# SH02_-_OMAP-L137_MCASP.net
KiCad netlist of a schematic drawn in Altium Designer
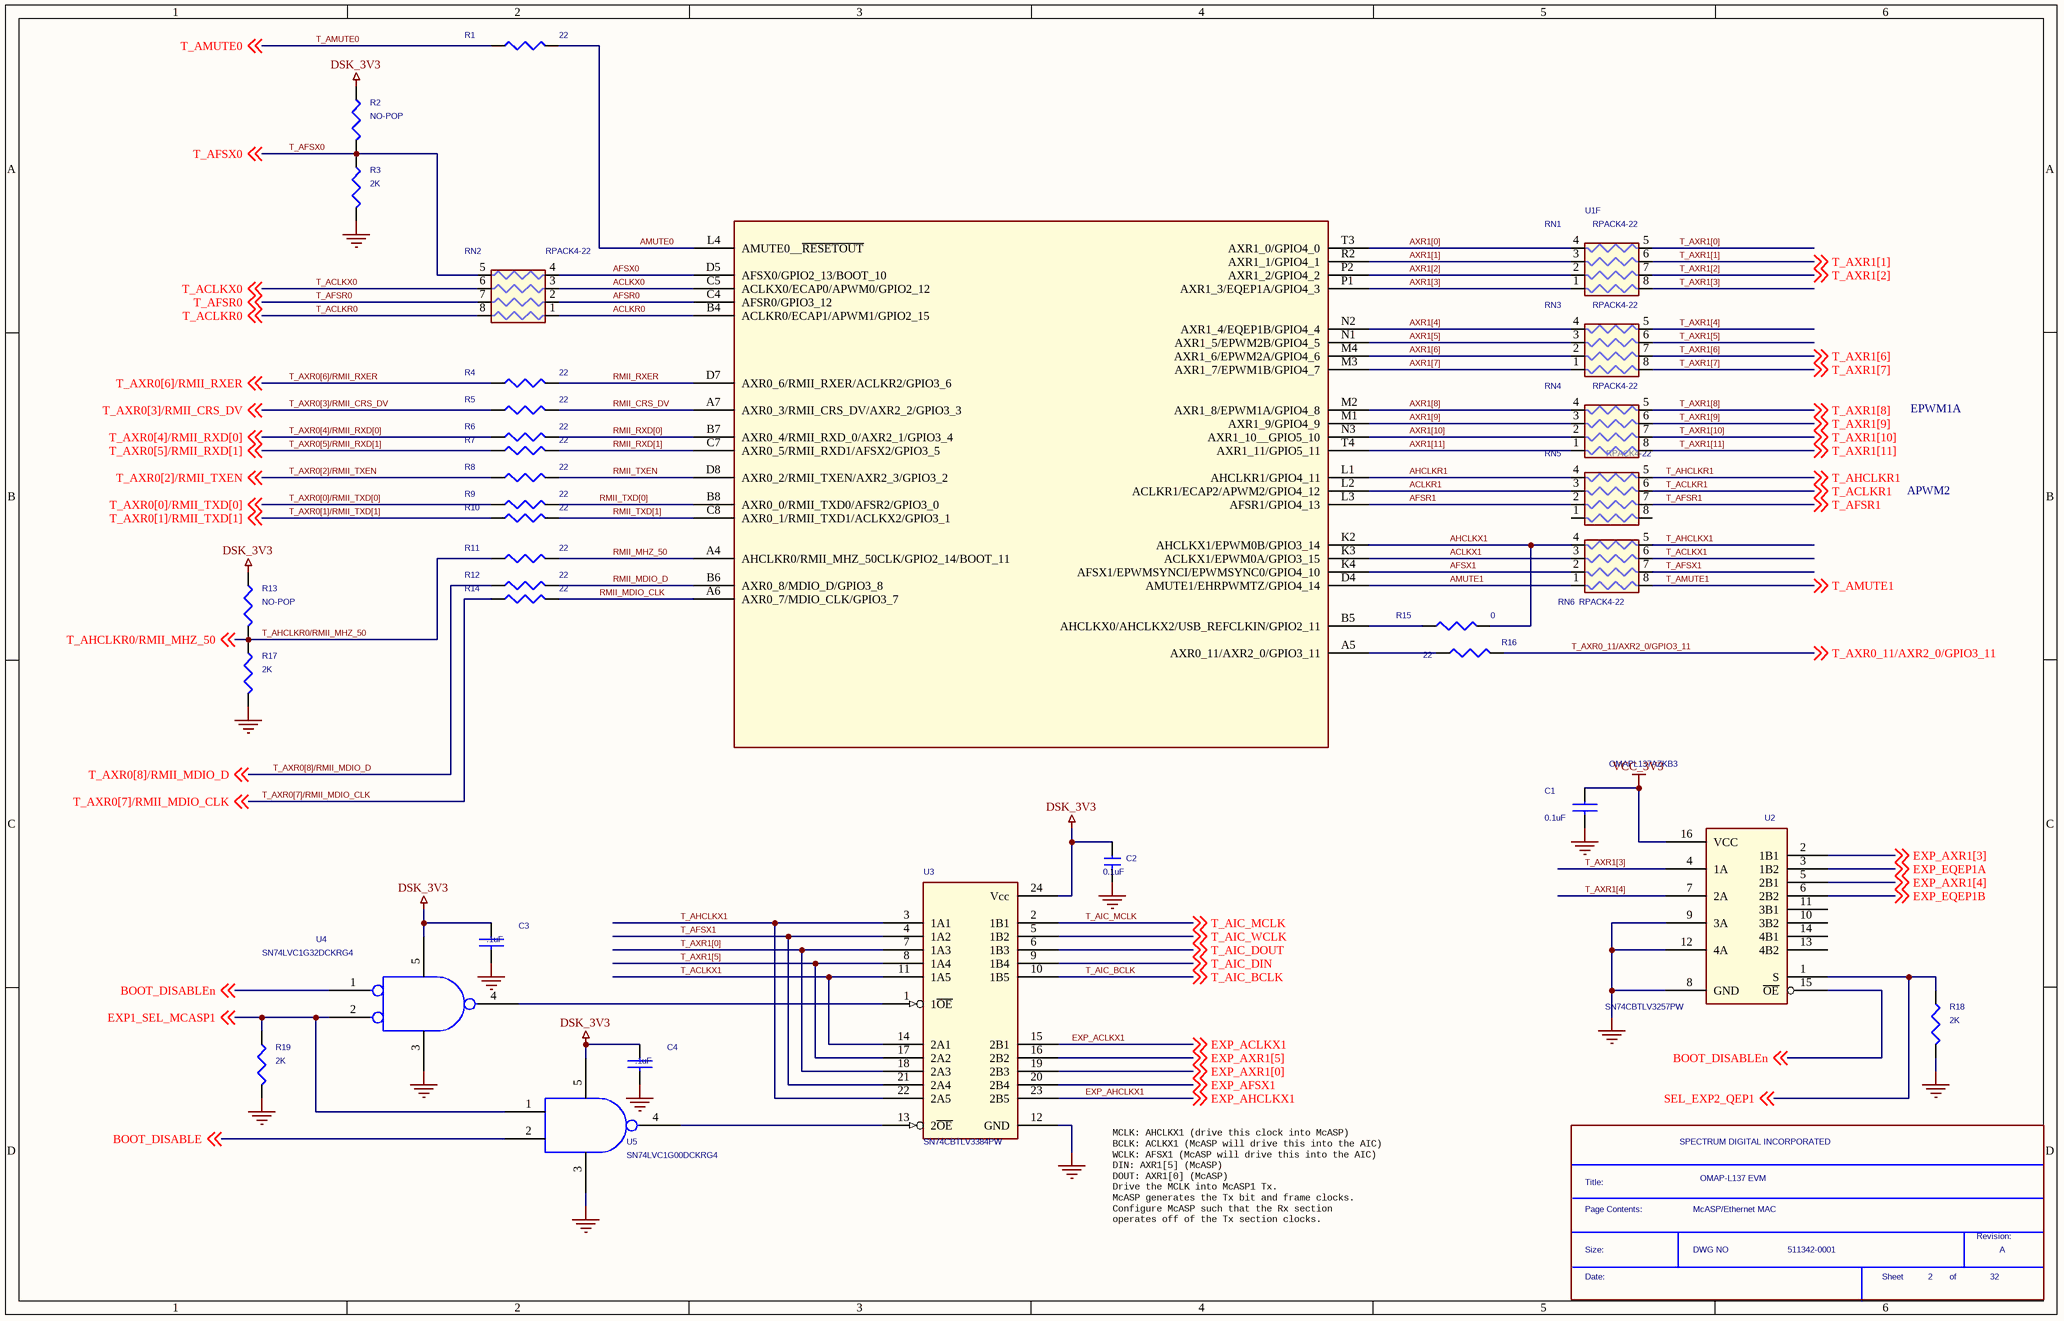
[diagram p0: SH02 - OMAP-L137 MCASP.SchDoc]

(export (version "E")
  (design (tool "Eeschema 10.0.6"))
  (components
    (comp (ref "C1")
      (value "0.1uF")
      (footprint "c402-25")
      (fields (field (name "PART #") "101587-1100R"))
      (libsource (lib "*") (part "CAP NP"))
    )
    (comp (ref "C2")
      (value "0.1uF")
      (footprint "c402-25")
      (fields (field (name "PART #") "101587-1100R"))
      (libsource (lib "*") (part "CAP NP_1"))
    )
    (comp (ref "C3")
      (value ".1uF")
      (footprint "c402-25")
      (fields (field (name "PART #") "101587-1100R"))
      (libsource (lib "*") (part "CAP NP_2"))
    )
    (comp (ref "C4")
      (value ".1uF")
      (footprint "c402-25")
      (fields (field (name "PART #") "101587-1100R"))
      (libsource (lib "*") (part "CAP NP_2"))
    )
    (comp (ref "R1")
      (value "22")
      (footprint "r402-25")
      (fields (field (name "PART #") "101370-2200R"))
      (libsource (lib "*") (part "R"))
    )
    (comp (ref "R2")
      (value "NO-POP")
      (footprint "r402-25")
      (fields (field (name "PART #") "R0402-NOPOP"))
      (libsource (lib "*") (part "R_1"))
    )
    (comp (ref "R3")
      (value "2K")
      (footprint "r402-25")
      (fields (field (name "PART #") "101370-2002R"))
      (libsource (lib "*") (part "R_1"))
    )
    (comp (ref "R4")
      (value "22")
      (footprint "r402-25")
      (fields (field (name "PART #") "101370-2200R"))
      (libsource (lib "*") (part "R"))
    )
    (comp (ref "R5")
      (value "22")
      (footprint "r402-25")
      (fields (field (name "PART #") "101370-2200R"))
      (libsource (lib "*") (part "R"))
    )
    (comp (ref "R6")
      (value "22")
      (footprint "r402-25")
      (fields (field (name "PART #") "101370-2200R"))
      (libsource (lib "*") (part "R"))
    )
    (comp (ref "R7")
      (value "22")
      (footprint "r402-25")
      (fields (field (name "PART #") "101370-2200R"))
      (libsource (lib "*") (part "R"))
    )
    (comp (ref "R8")
      (value "22")
      (footprint "r402-25")
      (fields (field (name "PART #") "101370-2200R"))
      (libsource (lib "*") (part "R"))
    )
    (comp (ref "R9")
      (value "22")
      (footprint "r402-25")
      (fields (field (name "PART #") "101370-2200R"))
      (libsource (lib "*") (part "R"))
    )
    (comp (ref "R10")
      (value "22")
      (footprint "r402-25")
      (fields (field (name "PART #") "101370-2200R"))
      (libsource (lib "*") (part "R"))
    )
    (comp (ref "R11")
      (value "22")
      (footprint "r402-25")
      (fields (field (name "PART #") "101370-2200R"))
      (libsource (lib "*") (part "R"))
    )
    (comp (ref "R12")
      (value "22")
      (footprint "r402-25")
      (fields (field (name "PART #") "101370-2200R"))
      (libsource (lib "*") (part "R"))
    )
    (comp (ref "R13")
      (value "NO-POP")
      (footprint "r402-25")
      (fields (field (name "PART #") "R0402-NOPOP"))
      (libsource (lib "*") (part "R_1"))
    )
    (comp (ref "R14")
      (value "22")
      (footprint "r402-25")
      (fields (field (name "PART #") "101370-2200R"))
      (libsource (lib "*") (part "R"))
    )
    (comp (ref "R15")
      (value "0")
      (footprint "r402-25")
      (fields (field (name "PART #") "101370-0001R"))
      (libsource (lib "*") (part "R"))
    )
    (comp (ref "R16")
      (value "22")
      (footprint "r402-25")
      (fields (field (name "PART #") "101370-2200R"))
      (libsource (lib "*") (part "R"))
    )
    (comp (ref "R17")
      (value "2K")
      (footprint "r402-25")
      (fields (field (name "PART #") "101370-2002R"))
      (libsource (lib "*") (part "R_1"))
    )
    (comp (ref "R18")
      (value "2K")
      (footprint "r402-25")
      (fields (field (name "PART #") "101370-2002R"))
      (libsource (lib "*") (part "R"))
    )
    (comp (ref "R19")
      (value "2K")
      (footprint "r402-25")
      (fields (field (name "PART #") "101370-2002R"))
      (libsource (lib "*") (part "R"))
    )
    (comp (ref "RN1")
      (value "RPACK4-22")
      (footprint "rpak8-10x25-28v")
      (fields (field (name "PART #") "101327-2200R"))
      (libsource (lib "*") (part "R-Pak4_0"))
    )
    (comp (ref "RN2")
      (value "RPACK4-22")
      (footprint "rpak8-10x25-28v")
      (fields (field (name "PART #") "101327-2200R"))
      (libsource (lib "*") (part "R-Pak4_0"))
    )
    (comp (ref "RN3")
      (value "RPACK4-22")
      (footprint "rpak8-10x25-28v")
      (fields (field (name "PART #") "101327-2200R"))
      (libsource (lib "*") (part "R-Pak4_0"))
    )
    (comp (ref "RN4")
      (value "RPACK4-22")
      (footprint "rpak8-10x25-28v")
      (fields (field (name "PART #") "101327-2200R"))
      (libsource (lib "*") (part "R-Pak4_0"))
    )
    (comp (ref "RN5")
      (value "RPACK4-22")
      (footprint "rpak8-10x25-28v")
      (fields (field (name "PART #") "101327-2200R"))
      (libsource (lib "*") (part "R-Pak4_0"))
    )
    (comp (ref "RN6")
      (value "RPACK4-22")
      (footprint "rpak8-10x25-28v")
      (fields (field (name "PART #") "101327-2200R"))
      (libsource (lib "*") (part "R-Pak4_0"))
    )
    (comp (ref "U1")
      (value "OMAPL137AZKB3")
      (footprint "skt256-6064")
      (fields (field (name "PART #") "102772-0001"))
      (libsource (lib "*") (part "PRIMUS_BGA_1"))
    )
    (comp (ref "U2")
      (value "SN74CBTLV3257PW")
      (footprint "TSSOP-16")
      (description "IC, Quad 2-1 Multiplexer")
      (fields (field (name "MFG") "TI") (field (name "PART #") "101670-0001R"))
      (libsource (lib "*") (part "SN74CBT3257PW"))
    )
    (comp (ref "U3")
      (value "SN74CBTLV3384PW")
      (footprint "TSSOP-24")
      (description "IC, Quad 2-to-1 Mux with Level Conversion")
      (fields (field (name "PART #") "101679-0001R") (field (name "MFG") "TI"))
      (libsource (lib "*") (part "SN74CBTD3384PW"))
    )
    (comp (ref "U4")
      (value "SN74LVC1G32DCKRG4")
      (footprint "dck-5")
      (fields (field (name "PART #") "101057-0032R"))
      (libsource (lib "*") (part "1g32neg"))
    )
    (comp (ref "U5")
      (value "SN74LVC1G00DCKRG4")
      (footprint "dck-5")
      (fields (field (name "PART #") "101057-0001R"))
      (libsource (lib "*") (part "1g00_0"))
    )
  )
  (nets
    (net (code "1") (name "/ACLKR0") (class "Default")
      (node (ref "RN2") (pin "1") (pinfunction "R1A_1") (pintype "passive"))
      (node (ref "U1") (pin "B4") (pinfunction "ACLKR0/ECAP1/APWM1/GPIO2_15_B4") (pintype "passive"))
    )
    (net (code "2") (name "/ACLKR1") (class "Default")
      (node (ref "RN5") (pin "3") (pinfunction "R3A_3") (pintype "passive"))
      (node (ref "U1") (pin "L2") (pinfunction "ACLKR1/ECAP2/APWM2/GPIO4_12_L2") (pintype "passive"))
    )
    (net (code "3") (name "/ACLKX0") (class "Default")
      (node (ref "RN2") (pin "3") (pinfunction "R3A_3") (pintype "passive"))
      (node (ref "U1") (pin "C5") (pinfunction "ACLKX0/ECAP0/APWM0/GPIO2_12_C5") (pintype "passive"))
    )
    (net (code "4") (name "/ACLKX1") (class "Default")
      (node (ref "RN6") (pin "3") (pinfunction "R3A_3") (pintype "passive"))
      (node (ref "U1") (pin "K3") (pinfunction "ACLKX1/EPWM0A/GPIO3_15_K3") (pintype "passive"))
    )
    (net (code "5") (name "/AFSR0") (class "Default")
      (node (ref "RN2") (pin "2") (pinfunction "R2A_2") (pintype "passive"))
      (node (ref "U1") (pin "C4") (pinfunction "AFSR0/GPIO3_12_C4") (pintype "passive"))
    )
    (net (code "6") (name "/AFSR1") (class "Default")
      (node (ref "RN5") (pin "2") (pinfunction "R2A_2") (pintype "passive"))
      (node (ref "U1") (pin "L3") (pinfunction "AFSR1/GPIO4_13_L3") (pintype "passive"))
    )
    (net (code "7") (name "/AFSX0") (class "Default")
      (node (ref "RN2") (pin "4") (pinfunction "R4A_4") (pintype "passive"))
      (node (ref "U1") (pin "D5") (pinfunction "AFSX0/GPIO2_13/BOOT_10_D5") (pintype "passive"))
    )
    (net (code "8") (name "/AFSX1") (class "Default")
      (node (ref "RN6") (pin "2") (pinfunction "R2A_2") (pintype "passive"))
      (node (ref "U1") (pin "K4") (pinfunction "AFSX1/EPWMSYNCI/EPWMSYNC0/GPIO4_10_K4") (pintype "passive"))
    )
    (net (code "9") (name "/AHCLKR1") (class "Default")
      (node (ref "RN5") (pin "4") (pinfunction "R4A_4") (pintype "passive"))
      (node (ref "U1") (pin "L1") (pinfunction "AHCLKR1/GPIO4_11_L1") (pintype "passive"))
    )
    (net (code "10") (name "/AHCLKX1") (class "Default")
      (node (ref "R15") (pin "2") (pinfunction "2_2") (pintype "passive"))
      (node (ref "RN6") (pin "4") (pinfunction "R4A_4") (pintype "passive"))
      (node (ref "U1") (pin "K2") (pinfunction "AHCLKX1/EPWM0B/GPIO3_14_K2") (pintype "passive"))
    )
    (net (code "11") (name "/AMUTE0") (class "Default")
      (node (ref "R1") (pin "2") (pinfunction "2_2") (pintype "passive"))
      (node (ref "U1") (pin "L4") (pinfunction "AMUTE0__~{RESETOUT}_L4") (pintype "passive"))
    )
    (net (code "12") (name "/AMUTE1") (class "Default")
      (node (ref "RN6") (pin "1") (pinfunction "R1A_1") (pintype "passive"))
      (node (ref "U1") (pin "D4") (pinfunction "AMUTE1/EHRPWMTZ/GPIO4_14_D4") (pintype "passive"))
    )
    (net (code "13") (name "/AXR1[0]") (class "Default")
      (node (ref "RN1") (pin "4") (pinfunction "R4A_4") (pintype "passive"))
      (node (ref "U1") (pin "T3") (pinfunction "AXR1_0/GPIO4_0_T3") (pintype "passive"))
    )
    (net (code "14") (name "/AXR1[1]") (class "Default")
      (node (ref "RN1") (pin "3") (pinfunction "R3A_3") (pintype "passive"))
      (node (ref "U1") (pin "R2") (pinfunction "AXR1_1/GPIO4_1_R2") (pintype "passive"))
    )
    (net (code "15") (name "/AXR1[2]") (class "Default")
      (node (ref "RN1") (pin "2") (pinfunction "R2A_2") (pintype "passive"))
      (node (ref "U1") (pin "P2") (pinfunction "AXR1_2/GPIO4_2_P2") (pintype "passive"))
    )
    (net (code "16") (name "/AXR1[3]") (class "Default")
      (node (ref "RN1") (pin "1") (pinfunction "R1A_1") (pintype "passive"))
      (node (ref "U1") (pin "P1") (pinfunction "AXR1_3/EQEP1A/GPIO4_3_P1") (pintype "passive"))
    )
    (net (code "17") (name "/AXR1[4]") (class "Default")
      (node (ref "RN3") (pin "4") (pinfunction "R4A_4") (pintype "passive"))
      (node (ref "U1") (pin "N2") (pinfunction "AXR1_4/EQEP1B/GPIO4_4_N2") (pintype "passive"))
    )
    (net (code "18") (name "/AXR1[5]") (class "Default")
      (node (ref "RN3") (pin "3") (pinfunction "R3A_3") (pintype "passive"))
      (node (ref "U1") (pin "N1") (pinfunction "AXR1_5/EPWM2B/GPIO4_5_N1") (pintype "passive"))
    )
    (net (code "19") (name "/AXR1[6]") (class "Default")
      (node (ref "RN3") (pin "2") (pinfunction "R2A_2") (pintype "passive"))
      (node (ref "U1") (pin "M4") (pinfunction "AXR1_6/EPWM2A/GPIO4_6_M4") (pintype "passive"))
    )
    (net (code "20") (name "/AXR1[7]") (class "Default")
      (node (ref "RN3") (pin "1") (pinfunction "R1A_1") (pintype "passive"))
      (node (ref "U1") (pin "M3") (pinfunction "AXR1_7/EPWM1B/GPIO4_7_M3") (pintype "passive"))
    )
    (net (code "21") (name "/AXR1[8]") (class "Default")
      (node (ref "RN4") (pin "4") (pinfunction "R4A_4") (pintype "passive"))
      (node (ref "U1") (pin "M2") (pinfunction "AXR1_8/EPWM1A/GPIO4_8_M2") (pintype "passive"))
    )
    (net (code "22") (name "/AXR1[9]") (class "Default")
      (node (ref "RN4") (pin "3") (pinfunction "R3A_3") (pintype "passive"))
      (node (ref "U1") (pin "M1") (pinfunction "AXR1_9/GPIO4_9_M1") (pintype "passive"))
    )
    (net (code "23") (name "/AXR1[10]") (class "Default")
      (node (ref "RN4") (pin "2") (pinfunction "R2A_2") (pintype "passive"))
      (node (ref "U1") (pin "N3") (pinfunction "AXR1_10__GPIO5_10_N3") (pintype "passive"))
    )
    (net (code "24") (name "/AXR1[11]") (class "Default")
      (node (ref "RN4") (pin "1") (pinfunction "R1A_1") (pintype "passive"))
      (node (ref "U1") (pin "T4") (pinfunction "AXR1_11/GPIO5_11_T4") (pintype "passive"))
    )
    (net (code "25") (name "/RMII_CRS_DV") (class "Default")
      (node (ref "R5") (pin "2") (pinfunction "2_2") (pintype "passive"))
      (node (ref "U1") (pin "A7") (pinfunction "AXR0_3/RMII_CRS_DV/AXR2_2/GPIO3_3_A7") (pintype "passive"))
    )
    (net (code "26") (name "/RMII_MDIO_CLK") (class "Default")
      (node (ref "R14") (pin "2") (pinfunction "2_2") (pintype "passive"))
      (node (ref "U1") (pin "A6") (pinfunction "AXR0_7/MDIO_CLK/GPIO3_7_A6") (pintype "passive"))
    )
    (net (code "27") (name "/RMII_MDIO_D") (class "Default")
      (node (ref "R12") (pin "2") (pinfunction "2_2") (pintype "passive"))
      (node (ref "U1") (pin "B6") (pinfunction "AXR0_8/MDIO_D/GPIO3_8_B6") (pintype "passive"))
    )
    (net (code "28") (name "/RMII_MHZ_50") (class "Default")
      (node (ref "R11") (pin "2") (pinfunction "2_2") (pintype "passive"))
      (node (ref "U1") (pin "A4") (pinfunction "AHCLKR0/RMII_MHZ_50CLK/GPIO2_14/BOOT_11_A4") (pintype "passive"))
    )
    (net (code "29") (name "/RMII_RXD[0]") (class "Default")
      (node (ref "R6") (pin "2") (pinfunction "2_2") (pintype "passive"))
      (node (ref "U1") (pin "B7") (pinfunction "AXR0_4/RMII_RXD_0/AXR2_1/GPIO3_4_B7") (pintype "passive"))
    )
    (net (code "30") (name "/RMII_RXD[1]") (class "Default")
      (node (ref "R7") (pin "2") (pinfunction "2_2") (pintype "passive"))
      (node (ref "U1") (pin "C7") (pinfunction "AXR0_5/RMII_RXD1/AFSX2/GPIO3_5_C7") (pintype "passive"))
    )
    (net (code "31") (name "/RMII_RXER") (class "Default")
      (node (ref "R4") (pin "2") (pinfunction "2_2") (pintype "passive"))
      (node (ref "U1") (pin "D7") (pinfunction "AXR0_6/RMII_RXER/ACLKR2/GPIO3_6_D7") (pintype "passive"))
    )
    (net (code "32") (name "/RMII_TXD[0]") (class "Default")
      (node (ref "R9") (pin "2") (pinfunction "2_2") (pintype "passive"))
      (node (ref "U1") (pin "B8") (pinfunction "AXR0_0/RMII_TXD0/AFSR2/GPIO3_0_B8") (pintype "passive"))
    )
    (net (code "33") (name "/RMII_TXD[1]") (class "Default")
      (node (ref "R10") (pin "2") (pinfunction "2_2") (pintype "passive"))
      (node (ref "U1") (pin "C8") (pinfunction "AXR0_1/RMII_TXD1/ACLKX2/GPIO3_1_C8") (pintype "passive"))
    )
    (net (code "34") (name "/RMII_TXEN") (class "Default")
      (node (ref "R8") (pin "2") (pinfunction "2_2") (pintype "passive"))
      (node (ref "U1") (pin "D8") (pinfunction "AXR0_2/RMII_TXEN/AXR2_3/GPIO3_2_D8") (pintype "passive"))
    )
    (net (code "35") (name "/T_ACLKX1") (class "Default")
      (node (ref "RN6") (pin "6") (pinfunction "R3B_6") (pintype "passive"))
      (node (ref "U3") (pin "11") (pinfunction "1A5_11") (pintype "passive"))
      (node (ref "U3") (pin "14") (pinfunction "2A1_14") (pintype "passive"))
    )
    (net (code "36") (name "/T_AFSX1") (class "Default")
      (node (ref "RN6") (pin "7") (pinfunction "R2B_7") (pintype "passive"))
      (node (ref "U3") (pin "21") (pinfunction "2A4_21") (pintype "passive"))
      (node (ref "U3") (pin "4") (pinfunction "1A2_4") (pintype "passive"))
    )
    (net (code "37") (name "/T_AHCLKX1") (class "Default")
      (node (ref "RN6") (pin "5") (pinfunction "R4B_5") (pintype "passive"))
      (node (ref "U3") (pin "22") (pinfunction "2A5_22") (pintype "passive"))
      (node (ref "U3") (pin "3") (pinfunction "1A1_3") (pintype "passive"))
    )
    (net (code "38") (name "/T_AXR1[0]") (class "Default")
      (node (ref "RN1") (pin "5") (pinfunction "R4B_5") (pintype "passive"))
      (node (ref "U3") (pin "18") (pinfunction "2A3_18") (pintype "passive"))
      (node (ref "U3") (pin "7") (pinfunction "1A3_7") (pintype "passive"))
    )
    (net (code "39") (name "/T_AXR1[3]") (class "Default")
      (node (ref "RN1") (pin "8") (pinfunction "R1B_8") (pintype "passive"))
      (node (ref "U2") (pin "4") (pinfunction "1A_4") (pintype "passive"))
    )
    (net (code "40") (name "/T_AXR1[4]") (class "Default")
      (node (ref "RN3") (pin "5") (pinfunction "R4B_5") (pintype "passive"))
      (node (ref "U2") (pin "7") (pinfunction "2A_7") (pintype "passive"))
    )
    (net (code "41") (name "/T_AXR1[5]") (class "Default")
      (node (ref "RN3") (pin "6") (pinfunction "R3B_6") (pintype "passive"))
      (node (ref "U3") (pin "17") (pinfunction "2A2_17") (pintype "passive"))
      (node (ref "U3") (pin "8") (pinfunction "1A4_8") (pintype "passive"))
    )
    (net (code "42") (name "BOOT_DISABLE") (class "Default")
      (node (ref "U5") (pin "2") (pinfunction "B_2") (pintype "passive"))
    )
    (net (code "43") (name "BOOT_DISABLEn") (class "Default")
      (node (ref "U2") (pin "15") (pinfunction "~{OE}_15") (pintype "passive"))
      (node (ref "U4") (pin "1") (pinfunction "A_1") (pintype "passive"))
    )
    (net (code "44") (name "DSK_3V3") (class "Default")
      (node (ref "C2") (pin "1") (pinfunction "1_1") (pintype "passive"))
      (node (ref "C3") (pin "1") (pinfunction "1_1") (pintype "passive"))
      (node (ref "C4") (pin "1") (pinfunction "1_1") (pintype "passive"))
      (node (ref "R13") (pin "1") (pinfunction "1_1") (pintype "passive"))
      (node (ref "R2") (pin "1") (pinfunction "1_1") (pintype "passive"))
      (node (ref "U3") (pin "24") (pinfunction "Vcc_24") (pintype "power_in"))
      (node (ref "U4") (pin "5") (pinfunction "VCC_5") (pintype "passive"))
      (node (ref "U5") (pin "5") (pinfunction "VCC_5") (pintype "passive"))
    )
    (net (code "45") (name "EXP1_SEL_MCASP1") (class "Default")
      (node (ref "R19") (pin "1") (pinfunction "1_1") (pintype "passive"))
      (node (ref "U4") (pin "2") (pinfunction "B_2") (pintype "passive"))
      (node (ref "U5") (pin "1") (pinfunction "A_1") (pintype "passive"))
    )
    (net (code "46") (name "EXP_ACLKX1") (class "Default")
      (node (ref "U3") (pin "15") (pinfunction "2B1_15") (pintype "passive"))
    )
    (net (code "47") (name "EXP_AFSX1") (class "Default")
      (node (ref "U3") (pin "20") (pinfunction "2B4_20") (pintype "passive"))
    )
    (net (code "48") (name "EXP_AHCLKX1") (class "Default")
      (node (ref "U3") (pin "23") (pinfunction "2B5_23") (pintype "passive"))
    )
    (net (code "49") (name "EXP_AXR1[0]") (class "Default")
      (node (ref "U3") (pin "19") (pinfunction "2B3_19") (pintype "passive"))
    )
    (net (code "50") (name "EXP_AXR1[3]") (class "Default")
      (node (ref "U2") (pin "2") (pinfunction "1B1_2") (pintype "passive"))
    )
    (net (code "51") (name "EXP_AXR1[4]") (class "Default")
      (node (ref "U2") (pin "5") (pinfunction "2B1_5") (pintype "passive"))
    )
    (net (code "52") (name "EXP_AXR1[5]") (class "Default")
      (node (ref "U3") (pin "16") (pinfunction "2B2_16") (pintype "passive"))
    )
    (net (code "53") (name "EXP_EQEP1A") (class "Default")
      (node (ref "U2") (pin "3") (pinfunction "1B2_3") (pintype "passive"))
    )
    (net (code "54") (name "EXP_EQEP1B") (class "Default")
      (node (ref "U2") (pin "6") (pinfunction "2B2_6") (pintype "passive"))
    )
    (net (code "55") (name "GND") (class "Default")
      (node (ref "C1") (pin "2") (pinfunction "2_2") (pintype "passive"))
      (node (ref "C2") (pin "2") (pinfunction "2_2") (pintype "passive"))
      (node (ref "C3") (pin "2") (pinfunction "2_2") (pintype "passive"))
      (node (ref "C4") (pin "2") (pinfunction "2_2") (pintype "passive"))
      (node (ref "R17") (pin "2") (pinfunction "2_2") (pintype "passive"))
      (node (ref "R18") (pin "2") (pinfunction "2_2") (pintype "passive"))
      (node (ref "R19") (pin "2") (pinfunction "2_2") (pintype "passive"))
      (node (ref "R3") (pin "2") (pinfunction "2_2") (pintype "passive"))
      (node (ref "U2") (pin "12") (pinfunction "4A_12") (pintype "passive"))
      (node (ref "U2") (pin "8") (pinfunction "GND_8") (pintype "passive"))
      (node (ref "U2") (pin "9") (pinfunction "3A_9") (pintype "passive"))
      (node (ref "U3") (pin "12") (pinfunction "GND_12") (pintype "power_in"))
      (node (ref "U4") (pin "3") (pinfunction "GND_3") (pintype "passive"))
      (node (ref "U5") (pin "3") (pinfunction "GND_3") (pintype "passive"))
    )
    (net (code "56") (name "Net-(U1F-AHCLKX0{slash}AHCLKX2{slash}USB_REFCLKIN{slash}GPIO2_11)") (class "Default")
      (node (ref "R15") (pin "1") (pinfunction "1_1") (pintype "passive"))
      (node (ref "U1") (pin "B5") (pinfunction "AHCLKX0/AHCLKX2/USB_REFCLKIN/GPIO2_11_B5") (pintype "passive"))
    )
    (net (code "57") (name "Net-(U1F-AXR0_11{slash}AXR2_0{slash}GPIO3_11)") (class "Default")
      (node (ref "R16") (pin "2") (pinfunction "2_2") (pintype "passive"))
      (node (ref "U1") (pin "A5") (pinfunction "AXR0_11/AXR2_0/GPIO3_11_A5") (pintype "passive"))
    )
    (net (code "58") (name "Net-(U3-1~{OE})") (class "Default")
      (node (ref "U3") (pin "1") (pinfunction "1~{OE}_1") (pintype "input"))
      (node (ref "U4") (pin "4") (pinfunction "Y_4") (pintype "passive"))
    )
    (net (code "59") (name "Net-(U3-2~{OE})") (class "Default")
      (node (ref "U3") (pin "13") (pinfunction "2~{OE}_13") (pintype "input"))
      (node (ref "U5") (pin "4") (pinfunction "Y_4") (pintype "passive"))
    )
    (net (code "60") (name "SEL_EXP2_QEP1") (class "Default")
      (node (ref "R18") (pin "1") (pinfunction "1_1") (pintype "passive"))
      (node (ref "U2") (pin "1") (pinfunction "S_1") (pintype "passive"))
    )
    (net (code "61") (name "T_ACLKR0") (class "Default")
      (node (ref "RN2") (pin "8") (pinfunction "R1B_8") (pintype "passive"))
    )
    (net (code "62") (name "T_ACLKR1") (class "Default")
      (node (ref "RN5") (pin "6") (pinfunction "R3B_6") (pintype "passive"))
    )
    (net (code "63") (name "T_ACLKX0") (class "Default")
      (node (ref "RN2") (pin "6") (pinfunction "R3B_6") (pintype "passive"))
    )
    (net (code "64") (name "T_AFSR0") (class "Default")
      (node (ref "RN2") (pin "7") (pinfunction "R2B_7") (pintype "passive"))
    )
    (net (code "65") (name "T_AFSR1") (class "Default")
      (node (ref "RN5") (pin "7") (pinfunction "R2B_7") (pintype "passive"))
    )
    (net (code "66") (name "T_AFSX0") (class "Default")
      (node (ref "R2") (pin "2") (pinfunction "2_2") (pintype "passive"))
      (node (ref "R3") (pin "1") (pinfunction "1_1") (pintype "passive"))
      (node (ref "RN2") (pin "5") (pinfunction "R4B_5") (pintype "passive"))
    )
    (net (code "67") (name "T_AHCLKR0{slash}RMII_MHZ_50") (class "Default")
      (node (ref "R11") (pin "1") (pinfunction "1_1") (pintype "passive"))
      (node (ref "R13") (pin "2") (pinfunction "2_2") (pintype "passive"))
      (node (ref "R17") (pin "1") (pinfunction "1_1") (pintype "passive"))
    )
    (net (code "68") (name "T_AHCLKR1") (class "Default")
      (node (ref "RN5") (pin "5") (pinfunction "R4B_5") (pintype "passive"))
    )
    (net (code "69") (name "T_AIC_BCLK") (class "Default")
      (node (ref "U3") (pin "10") (pinfunction "1B5_10") (pintype "passive"))
    )
    (net (code "70") (name "T_AIC_DIN") (class "Default")
      (node (ref "U3") (pin "9") (pinfunction "1B4_9") (pintype "passive"))
    )
    (net (code "71") (name "T_AIC_DOUT") (class "Default")
      (node (ref "U3") (pin "6") (pinfunction "1B3_6") (pintype "passive"))
    )
    (net (code "72") (name "T_AIC_MCLK") (class "Default")
      (node (ref "U3") (pin "2") (pinfunction "1B1_2") (pintype "passive"))
    )
    (net (code "73") (name "T_AIC_WCLK") (class "Default")
      (node (ref "U3") (pin "5") (pinfunction "1B2_5") (pintype "passive"))
    )
    (net (code "74") (name "T_AMUTE0") (class "Default")
      (node (ref "R1") (pin "1") (pinfunction "1_1") (pintype "passive"))
    )
    (net (code "75") (name "T_AMUTE1") (class "Default")
      (node (ref "RN6") (pin "8") (pinfunction "R1B_8") (pintype "passive"))
    )
    (net (code "76") (name "T_AXR0[0]{slash}RMII_TXD[0]") (class "Default")
      (node (ref "R9") (pin "1") (pinfunction "1_1") (pintype "passive"))
    )
    (net (code "77") (name "T_AXR0[1]{slash}RMII_TXD[1]") (class "Default")
      (node (ref "R10") (pin "1") (pinfunction "1_1") (pintype "passive"))
    )
    (net (code "78") (name "T_AXR0[2]{slash}RMII_TXEN") (class "Default")
      (node (ref "R8") (pin "1") (pinfunction "1_1") (pintype "passive"))
    )
    (net (code "79") (name "T_AXR0[3]{slash}RMII_CRS_DV") (class "Default")
      (node (ref "R5") (pin "1") (pinfunction "1_1") (pintype "passive"))
    )
    (net (code "80") (name "T_AXR0[4]{slash}RMII_RXD[0]") (class "Default")
      (node (ref "R6") (pin "1") (pinfunction "1_1") (pintype "passive"))
    )
    (net (code "81") (name "T_AXR0[5]{slash}RMII_RXD[1]") (class "Default")
      (node (ref "R7") (pin "1") (pinfunction "1_1") (pintype "passive"))
    )
    (net (code "82") (name "T_AXR0[6]{slash}RMII_RXER") (class "Default")
      (node (ref "R4") (pin "1") (pinfunction "1_1") (pintype "passive"))
    )
    (net (code "83") (name "T_AXR0[7]{slash}RMII_MDIO_CLK") (class "Default")
      (node (ref "R14") (pin "1") (pinfunction "1_1") (pintype "passive"))
    )
    (net (code "84") (name "T_AXR0[8]{slash}RMII_MDIO_D") (class "Default")
      (node (ref "R12") (pin "1") (pinfunction "1_1") (pintype "passive"))
    )
    (net (code "85") (name "T_AXR0_11{slash}AXR2_0{slash}GPIO3_11") (class "Default")
      (node (ref "R16") (pin "1") (pinfunction "1_1") (pintype "passive"))
    )
    (net (code "86") (name "T_AXR1[1]") (class "Default")
      (node (ref "RN1") (pin "6") (pinfunction "R3B_6") (pintype "passive"))
    )
    (net (code "87") (name "T_AXR1[2]") (class "Default")
      (node (ref "RN1") (pin "7") (pinfunction "R2B_7") (pintype "passive"))
    )
    (net (code "88") (name "T_AXR1[6]") (class "Default")
      (node (ref "RN3") (pin "7") (pinfunction "R2B_7") (pintype "passive"))
    )
    (net (code "89") (name "T_AXR1[7]") (class "Default")
      (node (ref "RN3") (pin "8") (pinfunction "R1B_8") (pintype "passive"))
    )
    (net (code "90") (name "T_AXR1[8]") (class "Default")
      (node (ref "RN4") (pin "5") (pinfunction "R4B_5") (pintype "passive"))
    )
    (net (code "91") (name "T_AXR1[9]") (class "Default")
      (node (ref "RN4") (pin "6") (pinfunction "R3B_6") (pintype "passive"))
    )
    (net (code "92") (name "T_AXR1[10]") (class "Default")
      (node (ref "RN4") (pin "7") (pinfunction "R2B_7") (pintype "passive"))
    )
    (net (code "93") (name "T_AXR1[11]") (class "Default")
      (node (ref "RN4") (pin "8") (pinfunction "R1B_8") (pintype "passive"))
    )
    (net (code "94") (name "VCC_3V3") (class "Default")
      (node (ref "C1") (pin "1") (pinfunction "1_1") (pintype "passive"))
      (node (ref "U2") (pin "16") (pinfunction "VCC_16") (pintype "passive"))
    )
    (net (code "95") (name "unconnected-(RN5-R1A-Pad1)") (class "Default")
      (node (ref "RN5") (pin "1") (pinfunction "R1A_1") (pintype "passive"))
    )
    (net (code "96") (name "unconnected-(RN5-R1B-Pad8)") (class "Default")
      (node (ref "RN5") (pin "8") (pinfunction "R1B_8") (pintype "passive"))
    )
    (net (code "97") (name "unconnected-(U2-3B1-Pad11)") (class "Default")
      (node (ref "U2") (pin "11") (pinfunction "3B1_11") (pintype "passive"))
    )
    (net (code "98") (name "unconnected-(U2-3B2-Pad10)") (class "Default")
      (node (ref "U2") (pin "10") (pinfunction "3B2_10") (pintype "passive"))
    )
    (net (code "99") (name "unconnected-(U2-4B1-Pad14)") (class "Default")
      (node (ref "U2") (pin "14") (pinfunction "4B1_14") (pintype "passive"))
    )
    (net (code "100") (name "unconnected-(U2-4B2-Pad13)") (class "Default")
      (node (ref "U2") (pin "13") (pinfunction "4B2_13") (pintype "passive"))
    )
  )
)
